# STM32H730_PINOUT.net
KiCad netlist of a schematic drawn in Altium Designer
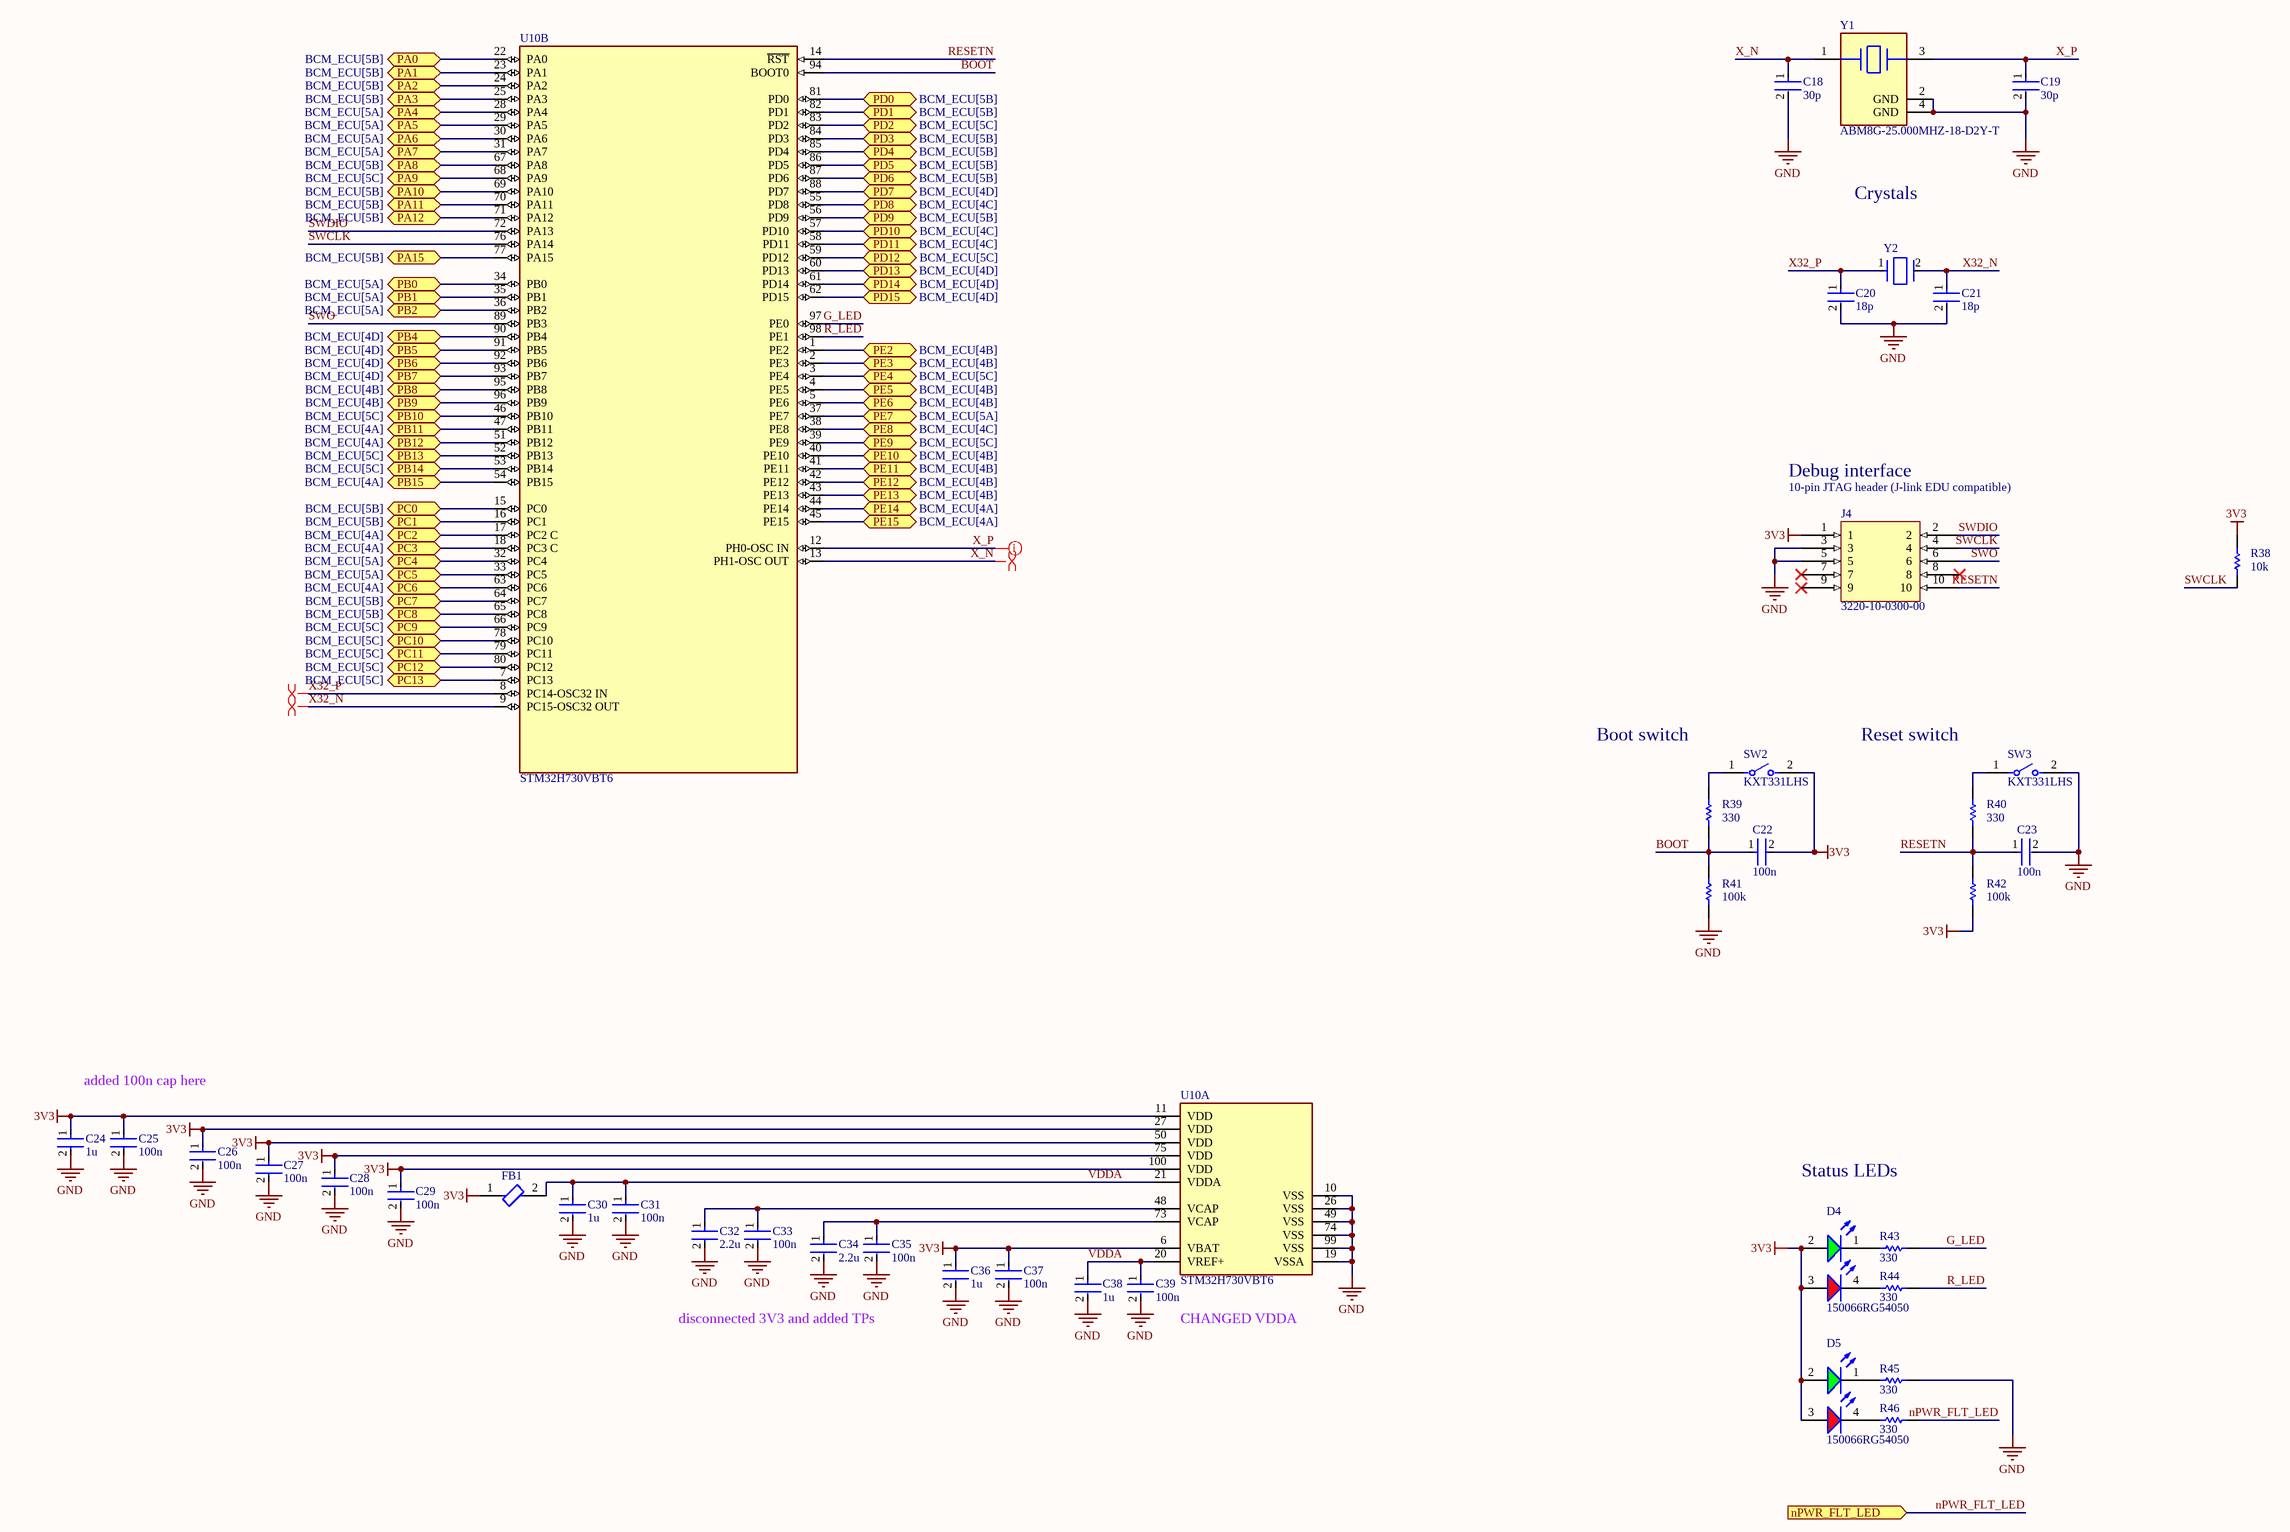
[diagram p0: STM32H730_PINOUT.SchDoc]

(export (version "E")
  (design (tool "Eeschema 10.0.6"))
  (components
    (comp (ref "C18")
      (value "30p")
      (footprint "FP-0402-L_1_0_0_05-W_0_5-IPC_A")
      (description "LARGE PADS, 0402 CAP, CHANGE COMMENT TO MATCH REAL P/N")
      (libsource (lib "Space Concordia") (part "b4654b650e69147ec39a6b967a45e02"))
    )
    (comp (ref "C19")
      (value "30p")
      (footprint "FP-0402-L_1_0_0_05-W_0_5-IPC_A")
      (description "LARGE PADS, 0402 CAP, CHANGE COMMENT TO MATCH REAL P/N")
      (libsource (lib "Space Concordia") (part "b4654b650e69147ec39a6b967a45e02"))
    )
    (comp (ref "C20")
      (value "18p")
      (footprint "FP-0402-L_1_0_0_05-W_0_5-IPC_A")
      (description "LARGE PADS, 0402 CAP, CHANGE COMMENT TO MATCH REAL P/N")
      (libsource (lib "Space Concordia") (part "b4654b650e69147ec39a6b967a45e02"))
    )
    (comp (ref "C21")
      (value "18p")
      (footprint "FP-0402-L_1_0_0_05-W_0_5-IPC_A")
      (description "LARGE PADS, 0402 CAP, CHANGE COMMENT TO MATCH REAL P/N")
      (libsource (lib "Space Concordia") (part "b4654b650e69147ec39a6b967a45e02"))
    )
    (comp (ref "C22")
      (value "100n")
      (footprint "FP-0402-L_1_0_0_05-W_0_5-IPC_A")
      (description "LARGE PADS, 0402 CAP, CHANGE COMMENT TO MATCH REAL P/N")
      (libsource (lib "Space Concordia") (part "b4654b650e69147ec39a6b967a45e02"))
    )
    (comp (ref "C23")
      (value "100n")
      (footprint "FP-0402-L_1_0_0_05-W_0_5-IPC_A")
      (description "LARGE PADS, 0402 CAP, CHANGE COMMENT TO MATCH REAL P/N")
      (libsource (lib "Space Concordia") (part "b4654b650e69147ec39a6b967a45e02"))
    )
    (comp (ref "C24")
      (value "1u")
      (footprint "FP-0402-L_1_0_0_05-W_0_5-IPC_A")
      (description "LARGE PADS, 0402 CAP, CHANGE COMMENT TO MATCH REAL P/N")
      (libsource (lib "Space Concordia") (part "b4654b650e69147ec39a6b967a45e02"))
    )
    (comp (ref "C25")
      (value "100n")
      (footprint "FP-0402-L_1_0_0_05-W_0_5-IPC_A")
      (description "LARGE PADS, 0402 CAP, CHANGE COMMENT TO MATCH REAL P/N")
      (libsource (lib "Space Concordia") (part "b4654b650e69147ec39a6b967a45e02"))
    )
    (comp (ref "C26")
      (value "100n")
      (footprint "FP-0402-L_1_0_0_05-W_0_5-IPC_A")
      (description "LARGE PADS, 0402 CAP, CHANGE COMMENT TO MATCH REAL P/N")
      (libsource (lib "Space Concordia") (part "b4654b650e69147ec39a6b967a45e02"))
    )
    (comp (ref "C27")
      (value "100n")
      (footprint "FP-0402-L_1_0_0_05-W_0_5-IPC_A")
      (description "LARGE PADS, 0402 CAP, CHANGE COMMENT TO MATCH REAL P/N")
      (libsource (lib "Space Concordia") (part "b4654b650e69147ec39a6b967a45e02"))
    )
    (comp (ref "C28")
      (value "100n")
      (footprint "FP-0402-L_1_0_0_05-W_0_5-IPC_A")
      (description "LARGE PADS, 0402 CAP, CHANGE COMMENT TO MATCH REAL P/N")
      (libsource (lib "Space Concordia") (part "b4654b650e69147ec39a6b967a45e02"))
    )
    (comp (ref "C29")
      (value "100n")
      (footprint "FP-0402-L_1_0_0_05-W_0_5-IPC_A")
      (description "LARGE PADS, 0402 CAP, CHANGE COMMENT TO MATCH REAL P/N")
      (libsource (lib "Space Concordia") (part "b4654b650e69147ec39a6b967a45e02"))
    )
    (comp (ref "C30")
      (value "1u")
      (footprint "FP-0402-L_1_0_0_05-W_0_5-IPC_A")
      (description "LARGE PADS, 0402 CAP, CHANGE COMMENT TO MATCH REAL P/N")
      (libsource (lib "Space Concordia") (part "b4654b650e69147ec39a6b967a45e02"))
    )
    (comp (ref "C31")
      (value "100n")
      (footprint "FP-0402-L_1_0_0_05-W_0_5-IPC_A")
      (description "LARGE PADS, 0402 CAP, CHANGE COMMENT TO MATCH REAL P/N")
      (libsource (lib "Space Concordia") (part "b4654b650e69147ec39a6b967a45e02"))
    )
    (comp (ref "C32")
      (value "2.2u")
      (footprint "FP-0402-L_1_0_0_05-W_0_5-IPC_A")
      (description "LARGE PADS, 0402 CAP, CHANGE COMMENT TO MATCH REAL P/N")
      (libsource (lib "Space Concordia") (part "b4654b650e69147ec39a6b967a45e02"))
    )
    (comp (ref "C33")
      (value "100n")
      (footprint "FP-0402-L_1_0_0_05-W_0_5-IPC_A")
      (description "LARGE PADS, 0402 CAP, CHANGE COMMENT TO MATCH REAL P/N")
      (libsource (lib "Space Concordia") (part "b4654b650e69147ec39a6b967a45e02"))
    )
    (comp (ref "C34")
      (value "2.2u")
      (footprint "FP-0402-L_1_0_0_05-W_0_5-IPC_A")
      (description "LARGE PADS, 0402 CAP, CHANGE COMMENT TO MATCH REAL P/N")
      (libsource (lib "Space Concordia") (part "b4654b650e69147ec39a6b967a45e02"))
    )
    (comp (ref "C35")
      (value "100n")
      (footprint "FP-0402-L_1_0_0_05-W_0_5-IPC_A")
      (description "LARGE PADS, 0402 CAP, CHANGE COMMENT TO MATCH REAL P/N")
      (libsource (lib "Space Concordia") (part "b4654b650e69147ec39a6b967a45e02"))
    )
    (comp (ref "C36")
      (value "1u")
      (footprint "FP-0402-L_1_0_0_05-W_0_5-IPC_A")
      (description "LARGE PADS, 0402 CAP, CHANGE COMMENT TO MATCH REAL P/N")
      (libsource (lib "Space Concordia") (part "b4654b650e69147ec39a6b967a45e02"))
    )
    (comp (ref "C37")
      (value "100n")
      (footprint "FP-0402-L_1_0_0_05-W_0_5-IPC_A")
      (description "LARGE PADS, 0402 CAP, CHANGE COMMENT TO MATCH REAL P/N")
      (libsource (lib "Space Concordia") (part "b4654b650e69147ec39a6b967a45e02"))
    )
    (comp (ref "C38")
      (value "1u")
      (footprint "FP-0402-L_1_0_0_05-W_0_5-IPC_A")
      (description "LARGE PADS, 0402 CAP, CHANGE COMMENT TO MATCH REAL P/N")
      (libsource (lib "Space Concordia") (part "b4654b650e69147ec39a6b967a45e02"))
    )
    (comp (ref "C39")
      (value "100n")
      (footprint "FP-0402-L_1_0_0_05-W_0_5-IPC_A")
      (description "LARGE PADS, 0402 CAP, CHANGE COMMENT TO MATCH REAL P/N")
      (libsource (lib "Space Concordia") (part "b4654b650e69147ec39a6b967a45e02"))
    )
    (comp (ref "D4")
      (value "150066RG54050")
      (footprint "WL-SBCD_0606")
      (description "Led, Red/Grn, 180Mcd/230Mcd, 624Nm/525Nm Rohs Compliant: Yes")
      (fields (field (name "SOURCE") "rgled.SchLib"))
      (libsource (lib "Space Concordia") (part "CMP-004-00034-2"))
    )
    (comp (ref "D5")
      (value "150066RG54050")
      (footprint "WL-SBCD_0606")
      (description "Led, Red/Grn, 180Mcd/230Mcd, 624Nm/525Nm Rohs Compliant: Yes")
      (fields (field (name "SOURCE") "rgled.SchLib"))
      (libsource (lib "Space Concordia") (part "CMP-004-00034-2"))
    )
    (comp (ref "FB1")
      (value "BLM15PX601SN1D")
      (footprint "FP-BLM15-0_05-IPC_A")
      (description "Chip Ferrite Bead, 0402, 600Ω @ 100MHz, 0.23Ω, 25%, 900mA")
      (fields (field (name "TOLERANCE") "25%"))
      (libsource (lib "Altium Content Vault") (part "5f30dd21d616792df468990f7003faa"))
    )
    (comp (ref "J4")
      (value "3220-10-0300-00")
      (footprint "3220-10-0300-00-Footprint-1")
      (description "CONN HEADER SMD 10POS 1.27MM")
      (libsource (lib "Space Concordia") (part "3220-10-0300-00"))
    )
    (comp (ref "R38")
      (value "10k")
      (footprint "R0603B")
      (description "Resistor")
      (libsource (lib "Space Concordia") (part "Resistor"))
    )
    (comp (ref "R39")
      (value "330")
      (footprint "R0603B")
      (description "Resistor")
      (libsource (lib "Space Concordia") (part "Resistor"))
    )
    (comp (ref "R40")
      (value "330")
      (footprint "R0603B")
      (description "Resistor")
      (libsource (lib "Space Concordia") (part "Resistor"))
    )
    (comp (ref "R41")
      (value "100k")
      (footprint "R0603B")
      (description "Resistor")
      (libsource (lib "Space Concordia") (part "Resistor"))
    )
    (comp (ref "R42")
      (value "100k")
      (footprint "R0603B")
      (description "Resistor")
      (libsource (lib "Space Concordia") (part "Resistor"))
    )
    (comp (ref "R43")
      (value "330")
      (footprint "R0603B")
      (description "Resistor")
      (libsource (lib "Space Concordia") (part "Resistor"))
    )
    (comp (ref "R44")
      (value "330")
      (footprint "R0603B")
      (description "Resistor")
      (libsource (lib "Space Concordia") (part "Resistor"))
    )
    (comp (ref "R45")
      (value "330")
      (footprint "R0603B")
      (description "Resistor")
      (libsource (lib "Space Concordia") (part "Resistor"))
    )
    (comp (ref "R46")
      (value "330")
      (footprint "R0603B")
      (description "Resistor")
      (libsource (lib "Space Concordia") (part "Resistor"))
    )
    (comp (ref "SW2")
      (value "KXT331LHS")
      (footprint "FP-KXT331LHS-MFG")
      (description "SWITCH TACTILE SPST-NO 0.02A 15V")
      (libsource (lib "Altium Content Vault") (part "bb27bde45df87f1f469753f287ef5ae"))
    )
    (comp (ref "SW3")
      (value "KXT331LHS")
      (footprint "FP-KXT331LHS-MFG")
      (description "SWITCH TACTILE SPST-NO 0.02A 15V")
      (libsource (lib "Altium Content Vault") (part "bb27bde45df87f1f469753f287ef5ae"))
    )
    (comp (ref "U10")
      (value "STM32H730VBT6")
      (footprint "FP-LQFP100-1L-IPC_C")
      (description "IC MCU 32BIT 128KB FLASH 100LQFP")
      (libsource (lib "Altium Content Vault") (part "44dc6501260a4d92b846760feb66c20"))
    )
    (comp (ref "Y1")
      (value "ABM8G-25.000MHZ-18-D2Y-T")
      (footprint "FP-ABM8G-MFG")
      (description "Crystal 25MHz ±20ppm (Tol) ±30ppm (Stability) 18pF FUND 60Ω 4-Pin SMD T/R")
      (fields (field (name "TOLERANCE") "20ppm"))
      (libsource (lib "Altium Content Vault") (part "48e526d86b7f2615d98721063c72f49"))
    )
    (comp (ref "Y2")
      (value "ECS-.327-12.5-1210-TR")
      (footprint "FP-ECX-1210-MFG")
      (description "CRYSTAL 32.7680KHZ 12.5PF SMD")
      (fields
        (field (name "OCTOPART") "https://octopart.com/ecs-.327-12.5-1210-tr-ecs+international-81221340")
        (field (name "TOLERANCE") "20ppm")
      )
      (libsource (lib "Altium Content Vault") (part "99724985039315a44fd0d1401b84e49"))
    )
  )
  (nets
    (net (code "1") (name "/BOOT") (class "Default")
      (node (ref "C22") (pin "1") (pinfunction "1_1") (pintype "passive"))
      (node (ref "R39") (pin "1") (pinfunction "1_1") (pintype "passive"))
      (node (ref "R41") (pin "2") (pinfunction "2_2") (pintype "passive"))
      (node (ref "U10") (pin "94") (pinfunction "BOOT0_94") (pintype "input"))
    )
    (net (code "2") (name "/G_LED") (class "Default")
      (node (ref "R43") (pin "1") (pinfunction "1_1") (pintype "passive"))
      (node (ref "U10") (pin "97") (pinfunction "PE0_97") (pintype "bidirectional"))
    )
    (net (code "3") (name "/PA0") (class "Default")
      (node (ref "U10") (pin "22") (pinfunction "PA0_22") (pintype "bidirectional"))
    )
    (net (code "4") (name "/PA1") (class "Default")
      (node (ref "U10") (pin "23") (pinfunction "PA1_23") (pintype "bidirectional"))
    )
    (net (code "5") (name "/PA2") (class "Default")
      (node (ref "U10") (pin "24") (pinfunction "PA2_24") (pintype "bidirectional"))
    )
    (net (code "6") (name "/PA3") (class "Default")
      (node (ref "U10") (pin "25") (pinfunction "PA3_25") (pintype "bidirectional"))
    )
    (net (code "7") (name "/PA4") (class "Default")
      (node (ref "U10") (pin "28") (pinfunction "PA4_28") (pintype "bidirectional"))
    )
    (net (code "8") (name "/PA5") (class "Default")
      (node (ref "U10") (pin "29") (pinfunction "PA5_29") (pintype "bidirectional"))
    )
    (net (code "9") (name "/PA6") (class "Default")
      (node (ref "U10") (pin "30") (pinfunction "PA6_30") (pintype "bidirectional"))
    )
    (net (code "10") (name "/PA7") (class "Default")
      (node (ref "U10") (pin "31") (pinfunction "PA7_31") (pintype "bidirectional"))
    )
    (net (code "11") (name "/PA8") (class "Default")
      (node (ref "U10") (pin "67") (pinfunction "PA8_67") (pintype "bidirectional"))
    )
    (net (code "12") (name "/PA9") (class "Default")
      (node (ref "U10") (pin "68") (pinfunction "PA9_68") (pintype "bidirectional"))
    )
    (net (code "13") (name "/PA10") (class "Default")
      (node (ref "U10") (pin "69") (pinfunction "PA10_69") (pintype "bidirectional"))
    )
    (net (code "14") (name "/PA11") (class "Default")
      (node (ref "U10") (pin "70") (pinfunction "PA11_70") (pintype "bidirectional"))
    )
    (net (code "15") (name "/PA12") (class "Default")
      (node (ref "U10") (pin "71") (pinfunction "PA12_71") (pintype "bidirectional"))
    )
    (net (code "16") (name "/PA15") (class "Default")
      (node (ref "U10") (pin "77") (pinfunction "PA15_77") (pintype "bidirectional"))
    )
    (net (code "17") (name "/PB0") (class "Default")
      (node (ref "U10") (pin "34") (pinfunction "PB0_34") (pintype "bidirectional"))
    )
    (net (code "18") (name "/PB1") (class "Default")
      (node (ref "U10") (pin "35") (pinfunction "PB1_35") (pintype "bidirectional"))
    )
    (net (code "19") (name "/PB2") (class "Default")
      (node (ref "U10") (pin "36") (pinfunction "PB2_36") (pintype "bidirectional"))
    )
    (net (code "20") (name "/PB4") (class "Default")
      (node (ref "U10") (pin "90") (pinfunction "PB4_90") (pintype "bidirectional"))
    )
    (net (code "21") (name "/PB5") (class "Default")
      (node (ref "U10") (pin "91") (pinfunction "PB5_91") (pintype "bidirectional"))
    )
    (net (code "22") (name "/PB6") (class "Default")
      (node (ref "U10") (pin "92") (pinfunction "PB6_92") (pintype "bidirectional"))
    )
    (net (code "23") (name "/PB7") (class "Default")
      (node (ref "U10") (pin "93") (pinfunction "PB7_93") (pintype "bidirectional"))
    )
    (net (code "24") (name "/PB8") (class "Default")
      (node (ref "U10") (pin "95") (pinfunction "PB8_95") (pintype "bidirectional"))
    )
    (net (code "25") (name "/PB9") (class "Default")
      (node (ref "U10") (pin "96") (pinfunction "PB9_96") (pintype "bidirectional"))
    )
    (net (code "26") (name "/PB10") (class "Default")
      (node (ref "U10") (pin "46") (pinfunction "PB10_46") (pintype "bidirectional"))
    )
    (net (code "27") (name "/PB11") (class "Default")
      (node (ref "U10") (pin "47") (pinfunction "PB11_47") (pintype "bidirectional"))
    )
    (net (code "28") (name "/PB12") (class "Default")
      (node (ref "U10") (pin "51") (pinfunction "PB12_51") (pintype "bidirectional"))
    )
    (net (code "29") (name "/PB13") (class "Default")
      (node (ref "U10") (pin "52") (pinfunction "PB13_52") (pintype "bidirectional"))
    )
    (net (code "30") (name "/PB14") (class "Default")
      (node (ref "U10") (pin "53") (pinfunction "PB14_53") (pintype "bidirectional"))
    )
    (net (code "31") (name "/PB15") (class "Default")
      (node (ref "U10") (pin "54") (pinfunction "PB15_54") (pintype "bidirectional"))
    )
    (net (code "32") (name "/PC0") (class "Default")
      (node (ref "U10") (pin "15") (pinfunction "PC0_15") (pintype "bidirectional"))
    )
    (net (code "33") (name "/PC1") (class "Default")
      (node (ref "U10") (pin "16") (pinfunction "PC1_16") (pintype "bidirectional"))
    )
    (net (code "34") (name "/PC2") (class "Default")
      (node (ref "U10") (pin "17") (pinfunction "PC2_C_17") (pintype "bidirectional"))
    )
    (net (code "35") (name "/PC3") (class "Default")
      (node (ref "U10") (pin "18") (pinfunction "PC3_C_18") (pintype "bidirectional"))
    )
    (net (code "36") (name "/PC4") (class "Default")
      (node (ref "U10") (pin "32") (pinfunction "PC4_32") (pintype "bidirectional"))
    )
    (net (code "37") (name "/PC5") (class "Default")
      (node (ref "U10") (pin "33") (pinfunction "PC5_33") (pintype "bidirectional"))
    )
    (net (code "38") (name "/PC6") (class "Default")
      (node (ref "U10") (pin "63") (pinfunction "PC6_63") (pintype "bidirectional"))
    )
    (net (code "39") (name "/PC7") (class "Default")
      (node (ref "U10") (pin "64") (pinfunction "PC7_64") (pintype "bidirectional"))
    )
    (net (code "40") (name "/PC8") (class "Default")
      (node (ref "U10") (pin "65") (pinfunction "PC8_65") (pintype "bidirectional"))
    )
    (net (code "41") (name "/PC9") (class "Default")
      (node (ref "U10") (pin "66") (pinfunction "PC9_66") (pintype "bidirectional"))
    )
    (net (code "42") (name "/PC10") (class "Default")
      (node (ref "U10") (pin "78") (pinfunction "PC10_78") (pintype "bidirectional"))
    )
    (net (code "43") (name "/PC11") (class "Default")
      (node (ref "U10") (pin "79") (pinfunction "PC11_79") (pintype "bidirectional"))
    )
    (net (code "44") (name "/PC12") (class "Default")
      (node (ref "U10") (pin "80") (pinfunction "PC12_80") (pintype "bidirectional"))
    )
    (net (code "45") (name "/PC13") (class "Default")
      (node (ref "U10") (pin "7") (pinfunction "PC13_7") (pintype "bidirectional"))
    )
    (net (code "46") (name "/PD0") (class "Default")
      (node (ref "U10") (pin "81") (pinfunction "PD0_81") (pintype "bidirectional"))
    )
    (net (code "47") (name "/PD1") (class "Default")
      (node (ref "U10") (pin "82") (pinfunction "PD1_82") (pintype "bidirectional"))
    )
    (net (code "48") (name "/PD2") (class "Default")
      (node (ref "U10") (pin "83") (pinfunction "PD2_83") (pintype "bidirectional"))
    )
    (net (code "49") (name "/PD3") (class "Default")
      (node (ref "U10") (pin "84") (pinfunction "PD3_84") (pintype "bidirectional"))
    )
    (net (code "50") (name "/PD4") (class "Default")
      (node (ref "U10") (pin "85") (pinfunction "PD4_85") (pintype "bidirectional"))
    )
    (net (code "51") (name "/PD5") (class "Default")
      (node (ref "U10") (pin "86") (pinfunction "PD5_86") (pintype "bidirectional"))
    )
    (net (code "52") (name "/PD6") (class "Default")
      (node (ref "U10") (pin "87") (pinfunction "PD6_87") (pintype "bidirectional"))
    )
    (net (code "53") (name "/PD7") (class "Default")
      (node (ref "U10") (pin "88") (pinfunction "PD7_88") (pintype "bidirectional"))
    )
    (net (code "54") (name "/PD8") (class "Default")
      (node (ref "U10") (pin "55") (pinfunction "PD8_55") (pintype "bidirectional"))
    )
    (net (code "55") (name "/PD9") (class "Default")
      (node (ref "U10") (pin "56") (pinfunction "PD9_56") (pintype "bidirectional"))
    )
    (net (code "56") (name "/PD10") (class "Default")
      (node (ref "U10") (pin "57") (pinfunction "PD10_57") (pintype "bidirectional"))
    )
    (net (code "57") (name "/PD11") (class "Default")
      (node (ref "U10") (pin "58") (pinfunction "PD11_58") (pintype "bidirectional"))
    )
    (net (code "58") (name "/PD12") (class "Default")
      (node (ref "U10") (pin "59") (pinfunction "PD12_59") (pintype "bidirectional"))
    )
    (net (code "59") (name "/PD13") (class "Default")
      (node (ref "U10") (pin "60") (pinfunction "PD13_60") (pintype "bidirectional"))
    )
    (net (code "60") (name "/PD14") (class "Default")
      (node (ref "U10") (pin "61") (pinfunction "PD14_61") (pintype "bidirectional"))
    )
    (net (code "61") (name "/PD15") (class "Default")
      (node (ref "U10") (pin "62") (pinfunction "PD15_62") (pintype "bidirectional"))
    )
    (net (code "62") (name "/PE2") (class "Default")
      (node (ref "U10") (pin "1") (pinfunction "PE2_1") (pintype "bidirectional"))
    )
    (net (code "63") (name "/PE3") (class "Default")
      (node (ref "U10") (pin "2") (pinfunction "PE3_2") (pintype "bidirectional"))
    )
    (net (code "64") (name "/PE4") (class "Default")
      (node (ref "U10") (pin "3") (pinfunction "PE4_3") (pintype "bidirectional"))
    )
    (net (code "65") (name "/PE5") (class "Default")
      (node (ref "U10") (pin "4") (pinfunction "PE5_4") (pintype "bidirectional"))
    )
    (net (code "66") (name "/PE6") (class "Default")
      (node (ref "U10") (pin "5") (pinfunction "PE6_5") (pintype "bidirectional"))
    )
    (net (code "67") (name "/PE7") (class "Default")
      (node (ref "U10") (pin "37") (pinfunction "PE7_37") (pintype "bidirectional"))
    )
    (net (code "68") (name "/PE8") (class "Default")
      (node (ref "U10") (pin "38") (pinfunction "PE8_38") (pintype "bidirectional"))
    )
    (net (code "69") (name "/PE9") (class "Default")
      (node (ref "U10") (pin "39") (pinfunction "PE9_39") (pintype "bidirectional"))
    )
    (net (code "70") (name "/PE10") (class "Default")
      (node (ref "U10") (pin "40") (pinfunction "PE10_40") (pintype "bidirectional"))
    )
    (net (code "71") (name "/PE11") (class "Default")
      (node (ref "U10") (pin "41") (pinfunction "PE11_41") (pintype "bidirectional"))
    )
    (net (code "72") (name "/PE12") (class "Default")
      (node (ref "U10") (pin "42") (pinfunction "PE12_42") (pintype "bidirectional"))
    )
    (net (code "73") (name "/PE13") (class "Default")
      (node (ref "U10") (pin "43") (pinfunction "PE13_43") (pintype "bidirectional"))
    )
    (net (code "74") (name "/PE14") (class "Default")
      (node (ref "U10") (pin "44") (pinfunction "PE14_44") (pintype "bidirectional"))
    )
    (net (code "75") (name "/PE15") (class "Default")
      (node (ref "U10") (pin "45") (pinfunction "PE15_45") (pintype "bidirectional"))
    )
    (net (code "76") (name "/RESETN") (class "Default")
      (node (ref "C23") (pin "1") (pinfunction "1_1") (pintype "passive"))
      (node (ref "J4") (pin "10") (pinfunction "10_10") (pintype "input"))
      (node (ref "R40") (pin "1") (pinfunction "1_1") (pintype "passive"))
      (node (ref "R42") (pin "2") (pinfunction "2_2") (pintype "passive"))
      (node (ref "U10") (pin "14") (pinfunction "~{RST}_14") (pintype "input"))
    )
    (net (code "77") (name "/R_LED") (class "Default")
      (node (ref "R44") (pin "1") (pinfunction "1_1") (pintype "passive"))
      (node (ref "U10") (pin "98") (pinfunction "PE1_98") (pintype "bidirectional"))
    )
    (net (code "78") (name "/SWCLK") (class "Default")
      (node (ref "J4") (pin "4") (pinfunction "4_4") (pintype "input"))
      (node (ref "R38") (pin "1") (pinfunction "1_1") (pintype "passive"))
      (node (ref "U10") (pin "76") (pinfunction "PA14_76") (pintype "bidirectional"))
    )
    (net (code "79") (name "/SWDIO") (class "Default")
      (node (ref "J4") (pin "2") (pinfunction "2_2") (pintype "input"))
      (node (ref "U10") (pin "72") (pinfunction "PA13_72") (pintype "bidirectional"))
    )
    (net (code "80") (name "/SWO") (class "Default")
      (node (ref "J4") (pin "6") (pinfunction "6_6") (pintype "input"))
      (node (ref "U10") (pin "89") (pinfunction "PB3_89") (pintype "bidirectional"))
    )
    (net (code "81") (name "/VDDA") (class "Default")
      (node (ref "C30") (pin "1") (pinfunction "1_1") (pintype "passive"))
      (node (ref "C31") (pin "1") (pinfunction "1_1") (pintype "passive"))
      (node (ref "C38") (pin "1") (pinfunction "1_1") (pintype "passive"))
      (node (ref "C39") (pin "1") (pinfunction "1_1") (pintype "passive"))
      (node (ref "FB1") (pin "2") (pinfunction "2_2") (pintype "passive"))
      (node (ref "U10") (pin "20") (pinfunction "VREF+_20") (pintype "power_in"))
      (node (ref "U10") (pin "21") (pinfunction "VDDA_21") (pintype "power_in"))
    )
    (net (code "82") (name "/X32_N") (class "Default")
      (node (ref "C21") (pin "1") (pinfunction "1_1") (pintype "passive"))
      (node (ref "U10") (pin "9") (pinfunction "PC15-OSC32_OUT_9") (pintype "bidirectional"))
      (node (ref "Y2") (pin "2") (pinfunction "Out/In_2") (pintype "passive"))
    )
    (net (code "83") (name "/X32_P") (class "Default")
      (node (ref "C20") (pin "1") (pinfunction "1_1") (pintype "passive"))
      (node (ref "U10") (pin "8") (pinfunction "PC14-OSC32_IN_8") (pintype "bidirectional"))
      (node (ref "Y2") (pin "1") (pinfunction "In/Out_1") (pintype "passive"))
    )
    (net (code "84") (name "/X_N") (class "Default")
      (node (ref "C18") (pin "1") (pinfunction "1_1") (pintype "passive"))
      (node (ref "U10") (pin "13") (pinfunction "PH1-OSC_OUT_13") (pintype "bidirectional"))
      (node (ref "Y1") (pin "1") (pinfunction "1_1") (pintype "passive"))
    )
    (net (code "85") (name "/X_P") (class "Default")
      (node (ref "C19") (pin "1") (pinfunction "1_1") (pintype "passive"))
      (node (ref "U10") (pin "12") (pinfunction "PH0-OSC_IN_12") (pintype "bidirectional"))
      (node (ref "Y1") (pin "3") (pinfunction "3_3") (pintype "passive"))
    )
    (net (code "86") (name "/nPWR_FLT_LED") (class "Default")
      (node (ref "R46") (pin "1") (pinfunction "1_1") (pintype "passive"))
    )
    (net (code "87") (name "3V3") (class "Default")
      (node (ref "C22") (pin "2") (pinfunction "2_2") (pintype "passive"))
      (node (ref "C24") (pin "1") (pinfunction "1_1") (pintype "passive"))
      (node (ref "C25") (pin "1") (pinfunction "1_1") (pintype "passive"))
      (node (ref "C26") (pin "1") (pinfunction "1_1") (pintype "passive"))
      (node (ref "C27") (pin "1") (pinfunction "1_1") (pintype "passive"))
      (node (ref "C28") (pin "1") (pinfunction "1_1") (pintype "passive"))
      (node (ref "C29") (pin "1") (pinfunction "1_1") (pintype "passive"))
      (node (ref "C36") (pin "1") (pinfunction "1_1") (pintype "passive"))
      (node (ref "C37") (pin "1") (pinfunction "1_1") (pintype "passive"))
      (node (ref "D4") (pin "2") (pinfunction "A_2") (pintype "passive"))
      (node (ref "D4") (pin "3") (pinfunction "A_3") (pintype "passive"))
      (node (ref "D5") (pin "2") (pinfunction "A_2") (pintype "passive"))
      (node (ref "D5") (pin "3") (pinfunction "A_3") (pintype "passive"))
      (node (ref "FB1") (pin "1") (pinfunction "1_1") (pintype "passive"))
      (node (ref "J4") (pin "1") (pinfunction "1_1") (pintype "input"))
      (node (ref "R38") (pin "2") (pinfunction "2_2") (pintype "passive"))
      (node (ref "R42") (pin "1") (pinfunction "1_1") (pintype "passive"))
      (node (ref "SW2") (pin "2") (pinfunction "2_2") (pintype "passive"))
      (node (ref "U10") (pin "100") (pinfunction "VDD_100") (pintype "power_in"))
      (node (ref "U10") (pin "11") (pinfunction "VDD_11") (pintype "power_in"))
      (node (ref "U10") (pin "27") (pinfunction "VDD_27") (pintype "power_in"))
      (node (ref "U10") (pin "50") (pinfunction "VDD_50") (pintype "power_in"))
      (node (ref "U10") (pin "6") (pinfunction "VBAT_6") (pintype "power_in"))
      (node (ref "U10") (pin "75") (pinfunction "VDD_75") (pintype "power_in"))
    )
    (net (code "88") (name "GND") (class "Default")
      (node (ref "C18") (pin "2") (pinfunction "2_2") (pintype "passive"))
      (node (ref "C19") (pin "2") (pinfunction "2_2") (pintype "passive"))
      (node (ref "C20") (pin "2") (pinfunction "2_2") (pintype "passive"))
      (node (ref "C21") (pin "2") (pinfunction "2_2") (pintype "passive"))
      (node (ref "C23") (pin "2") (pinfunction "2_2") (pintype "passive"))
      (node (ref "C24") (pin "2") (pinfunction "2_2") (pintype "passive"))
      (node (ref "C25") (pin "2") (pinfunction "2_2") (pintype "passive"))
      (node (ref "C26") (pin "2") (pinfunction "2_2") (pintype "passive"))
      (node (ref "C27") (pin "2") (pinfunction "2_2") (pintype "passive"))
      (node (ref "C28") (pin "2") (pinfunction "2_2") (pintype "passive"))
      (node (ref "C29") (pin "2") (pinfunction "2_2") (pintype "passive"))
      (node (ref "C30") (pin "2") (pinfunction "2_2") (pintype "passive"))
      (node (ref "C31") (pin "2") (pinfunction "2_2") (pintype "passive"))
      (node (ref "C32") (pin "2") (pinfunction "2_2") (pintype "passive"))
      (node (ref "C33") (pin "2") (pinfunction "2_2") (pintype "passive"))
      (node (ref "C34") (pin "2") (pinfunction "2_2") (pintype "passive"))
      (node (ref "C35") (pin "2") (pinfunction "2_2") (pintype "passive"))
      (node (ref "C36") (pin "2") (pinfunction "2_2") (pintype "passive"))
      (node (ref "C37") (pin "2") (pinfunction "2_2") (pintype "passive"))
      (node (ref "C38") (pin "2") (pinfunction "2_2") (pintype "passive"))
      (node (ref "C39") (pin "2") (pinfunction "2_2") (pintype "passive"))
      (node (ref "J4") (pin "3") (pinfunction "3_3") (pintype "input"))
      (node (ref "J4") (pin "5") (pinfunction "5_5") (pintype "input"))
      (node (ref "R41") (pin "1") (pinfunction "1_1") (pintype "passive"))
      (node (ref "R45") (pin "1") (pinfunction "1_1") (pintype "passive"))
      (node (ref "SW3") (pin "2") (pinfunction "2_2") (pintype "passive"))
      (node (ref "U10") (pin "10") (pinfunction "VSS_10") (pintype "power_in"))
      (node (ref "U10") (pin "19") (pinfunction "VSSA_19") (pintype "power_in"))
      (node (ref "U10") (pin "26") (pinfunction "VSS_26") (pintype "power_in"))
      (node (ref "U10") (pin "49") (pinfunction "VSS_49") (pintype "power_in"))
      (node (ref "U10") (pin "74") (pinfunction "VSS_74") (pintype "power_in"))
      (node (ref "U10") (pin "99") (pinfunction "VSS_99") (pintype "power_in"))
      (node (ref "Y1") (pin "2") (pinfunction "GND_2") (pintype "power_in"))
      (node (ref "Y1") (pin "4") (pinfunction "GND_4") (pintype "power_in"))
    )
    (net (code "89") (name "Net-(C32-Pad1)") (class "Default")
      (node (ref "C32") (pin "1") (pinfunction "1_1") (pintype "passive"))
      (node (ref "C33") (pin "1") (pinfunction "1_1") (pintype "passive"))
      (node (ref "U10") (pin "48") (pinfunction "VCAP_48") (pintype "power_in"))
    )
    (net (code "90") (name "Net-(C34-Pad1)") (class "Default")
      (node (ref "C34") (pin "1") (pinfunction "1_1") (pintype "passive"))
      (node (ref "C35") (pin "1") (pinfunction "1_1") (pintype "passive"))
      (node (ref "U10") (pin "73") (pinfunction "VCAP_73") (pintype "power_in"))
    )
    (net (code "91") (name "Net-(D4-K-Pad1)") (class "Default")
      (node (ref "D4") (pin "1") (pinfunction "K_1") (pintype "passive"))
      (node (ref "R43") (pin "2") (pinfunction "2_2") (pintype "passive"))
    )
    (net (code "92") (name "Net-(D4-K-Pad4)") (class "Default")
      (node (ref "D4") (pin "4") (pinfunction "K_4") (pintype "passive"))
      (node (ref "R44") (pin "2") (pinfunction "2_2") (pintype "passive"))
    )
    (net (code "93") (name "Net-(D5-K-Pad1)") (class "Default")
      (node (ref "D5") (pin "1") (pinfunction "K_1") (pintype "passive"))
      (node (ref "R45") (pin "2") (pinfunction "2_2") (pintype "passive"))
    )
    (net (code "94") (name "Net-(D5-K-Pad4)") (class "Default")
      (node (ref "D5") (pin "4") (pinfunction "K_4") (pintype "passive"))
      (node (ref "R46") (pin "2") (pinfunction "2_2") (pintype "passive"))
    )
    (net (code "95") (name "Net-(R39-Pad2)") (class "Default")
      (node (ref "R39") (pin "2") (pinfunction "2_2") (pintype "passive"))
      (node (ref "SW2") (pin "1") (pinfunction "1_1") (pintype "passive"))
    )
    (net (code "96") (name "Net-(R40-Pad2)") (class "Default")
      (node (ref "R40") (pin "2") (pinfunction "2_2") (pintype "passive"))
      (node (ref "SW3") (pin "1") (pinfunction "1_1") (pintype "passive"))
    )
    (net (code "97") (name "unconnected-(J4-Pad7)") (class "Default")
      (node (ref "J4") (pin "7") (pinfunction "7_7") (pintype "input+no_connect"))
    )
    (net (code "98") (name "unconnected-(J4-Pad8)") (class "Default")
      (node (ref "J4") (pin "8") (pinfunction "8_8") (pintype "input+no_connect"))
    )
    (net (code "99") (name "unconnected-(J4-Pad9)") (class "Default")
      (node (ref "J4") (pin "9") (pinfunction "9_9") (pintype "input+no_connect"))
    )
  )
)
